# Morpheus_conector.net
KiCad netlist of a schematic drawn in Altium Designer
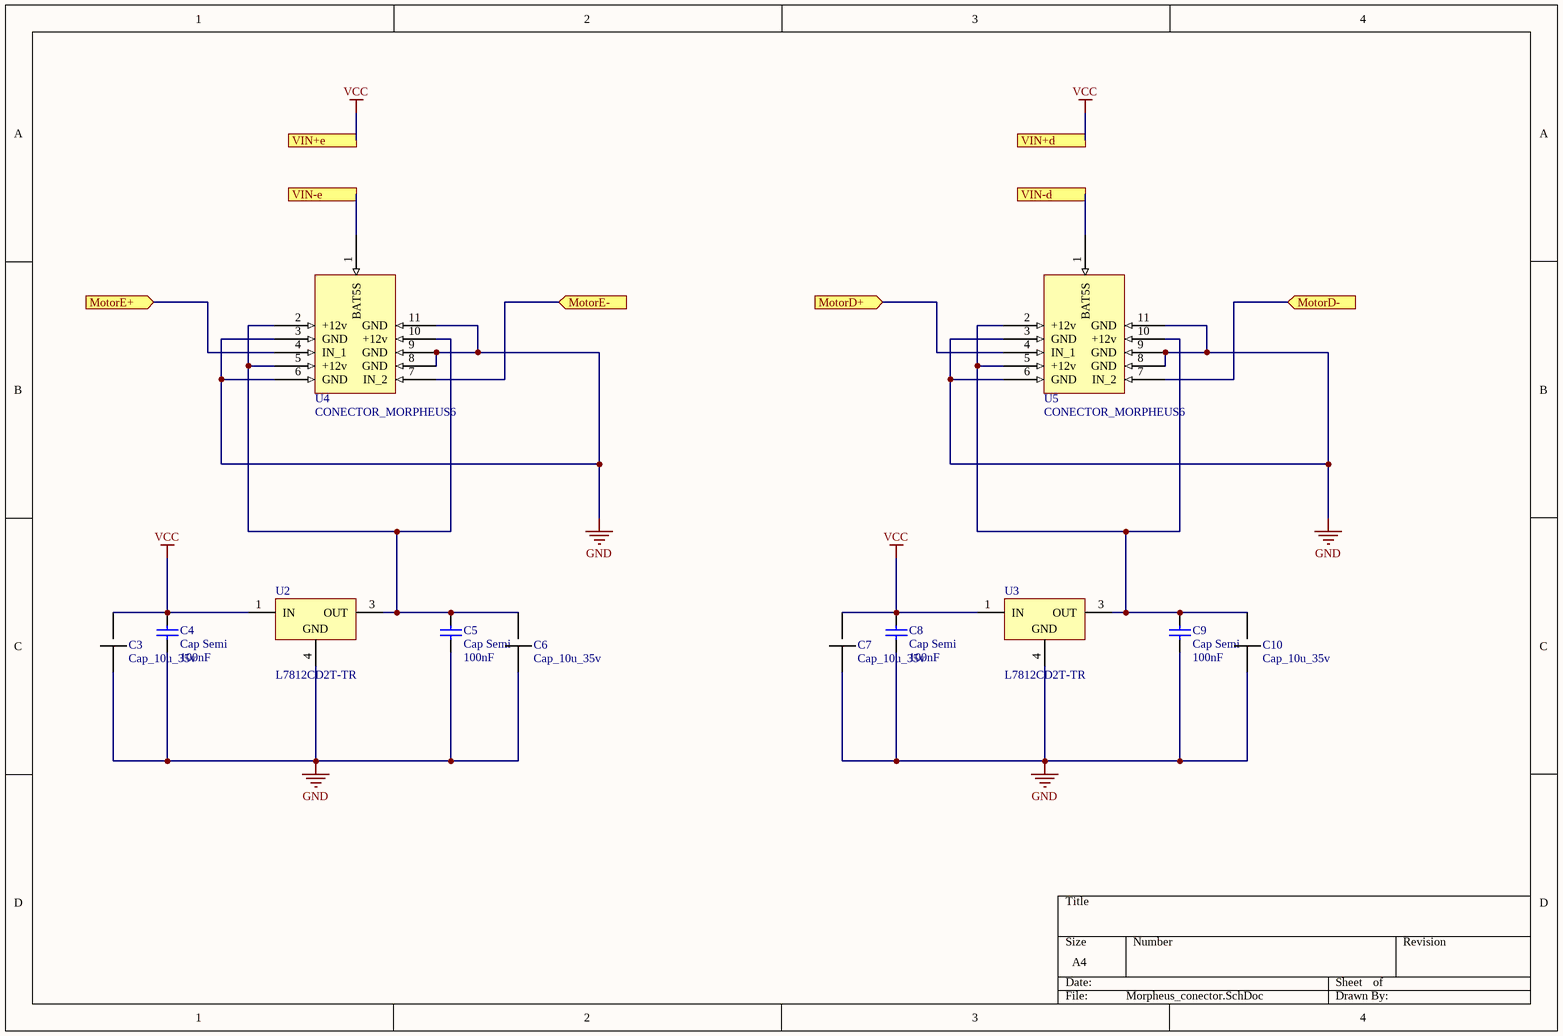
[diagram p0: Morpheus_conector.SchDoc]

(export (version "E")
  (design (tool "Eeschema 10.0.6"))
  (components
    (comp (ref "C3")
      (value "Cap_10u_35v")
      (footprint "Passives:CAP POL 2917/7343")
      (libsource (lib "LibSanhaço2017") (part "Cap_10u_35v"))
    )
    (comp (ref "C4")
      (value "Cap Semi")
      (footprint "C1206")
      (description "Capacitor (Semiconductor SIM Model)")
      (fields (field (name "ALTIUM_VALUE") "100nF") (field (name "PUBLISHER") "Altium Limited"))
      (libsource (lib "Miscellaneous Devices") (part "Cap Semi"))
    )
    (comp (ref "C5")
      (value "Cap Semi")
      (footprint "C1206")
      (description "Capacitor (Semiconductor SIM Model)")
      (fields (field (name "ALTIUM_VALUE") "100nF") (field (name "PUBLISHER") "Altium Limited"))
      (libsource (lib "Miscellaneous Devices") (part "Cap Semi"))
    )
    (comp (ref "C6")
      (value "Cap_10u_35v")
      (footprint "Passives:CAP POL 2917/7343")
      (libsource (lib "LibSanhaço2017") (part "Cap_10u_35v"))
    )
    (comp (ref "C7")
      (value "Cap_10u_35v")
      (footprint "Passives:CAP POL 2917/7343")
      (libsource (lib "LibSanhaço2017") (part "Cap_10u_35v"))
    )
    (comp (ref "C8")
      (value "Cap Semi")
      (footprint "C1206")
      (description "Capacitor (Semiconductor SIM Model)")
      (fields (field (name "ALTIUM_VALUE") "100nF") (field (name "PUBLISHER") "Altium Limited"))
      (libsource (lib "Miscellaneous Devices") (part "Cap Semi"))
    )
    (comp (ref "C9")
      (value "Cap Semi")
      (footprint "C1206")
      (description "Capacitor (Semiconductor SIM Model)")
      (fields (field (name "ALTIUM_VALUE") "100nF") (field (name "PUBLISHER") "Altium Limited"))
      (libsource (lib "Miscellaneous Devices") (part "Cap Semi"))
    )
    (comp (ref "C10")
      (value "Cap_10u_35v")
      (footprint "Passives:CAP POL 2917/7343")
      (libsource (lib "LibSanhaço2017") (part "Cap_10u_35v"))
    )
    (comp (ref "U2")
      (value "L7812CD2T-TR")
      (footprint "TO-263_N")
      (description "Positive Voltage Regulator, 3-Pin D2PAK, Tape and Reel")
      (libsource (lib "L7812CD2T-TR") (part "CMP-0244-00182-1"))
    )
    (comp (ref "U3")
      (value "L7812CD2T-TR")
      (footprint "TO-263_N")
      (description "Positive Voltage Regulator, 3-Pin D2PAK, Tape and Reel")
      (libsource (lib "L7812CD2T-TR") (part "CMP-0244-00182-1"))
    )
    (comp (ref "U4")
      (value "CONECTOR_MORPHEUS6")
      (libsource (lib "Morpheus_CONECTOR") (part "CONECTOR_MORPHEUS6"))
    )
    (comp (ref "U5")
      (value "CONECTOR_MORPHEUS6")
      (libsource (lib "Morpheus_CONECTOR") (part "CONECTOR_MORPHEUS6"))
    )
  )
  (nets
    (net (code "1") (name "/MotorD+") (class "Default")
      (node (ref "U5") (pin "4") (pinfunction "IN_1_4") (pintype "input"))
    )
    (net (code "2") (name "/MotorD-") (class "Default")
      (node (ref "U5") (pin "7") (pinfunction "IN_2_7") (pintype "input"))
    )
    (net (code "3") (name "/MotorE+") (class "Default")
      (node (ref "U4") (pin "4") (pinfunction "IN_1_4") (pintype "input"))
    )
    (net (code "4") (name "/MotorE-") (class "Default")
      (node (ref "U4") (pin "7") (pinfunction "IN_2_7") (pintype "input"))
    )
    (net (code "5") (name "/VIN-d") (class "Default")
      (node (ref "U5") (pin "1") (pinfunction "BAT5S_1") (pintype "input"))
    )
    (net (code "6") (name "/VIN-e") (class "Default")
      (node (ref "U4") (pin "1") (pinfunction "BAT5S_1") (pintype "input"))
    )
    (net (code "7") (name "GND") (class "Default")
      (node (ref "C10") (pin "1") (pinfunction "1_1") (pintype "passive"))
      (node (ref "C3") (pin "1") (pinfunction "1_1") (pintype "passive"))
      (node (ref "C4") (pin "1") (pinfunction "1_1") (pintype "passive"))
      (node (ref "C5") (pin "1") (pinfunction "1_1") (pintype "passive"))
      (node (ref "C6") (pin "1") (pinfunction "1_1") (pintype "passive"))
      (node (ref "C7") (pin "1") (pinfunction "1_1") (pintype "passive"))
      (node (ref "C8") (pin "1") (pinfunction "1_1") (pintype "passive"))
      (node (ref "C9") (pin "1") (pinfunction "1_1") (pintype "passive"))
      (node (ref "U2") (pin "4") (pinfunction "GND_4") (pintype "power_in"))
      (node (ref "U3") (pin "4") (pinfunction "GND_4") (pintype "power_in"))
      (node (ref "U4") (pin "11") (pinfunction "GND_11") (pintype "input"))
      (node (ref "U4") (pin "3") (pinfunction "GND_3") (pintype "input"))
      (node (ref "U4") (pin "6") (pinfunction "GND_6") (pintype "input"))
      (node (ref "U4") (pin "8") (pinfunction "GND_8") (pintype "input"))
      (node (ref "U4") (pin "9") (pinfunction "GND_9") (pintype "input"))
      (node (ref "U5") (pin "11") (pinfunction "GND_11") (pintype "input"))
      (node (ref "U5") (pin "3") (pinfunction "GND_3") (pintype "input"))
      (node (ref "U5") (pin "6") (pinfunction "GND_6") (pintype "input"))
      (node (ref "U5") (pin "8") (pinfunction "GND_8") (pintype "input"))
      (node (ref "U5") (pin "9") (pinfunction "GND_9") (pintype "input"))
    )
    (net (code "8") (name "Net-(U2-OUT)") (class "Default")
      (node (ref "C5") (pin "2") (pinfunction "2_2") (pintype "passive"))
      (node (ref "C6") (pin "2") (pinfunction "2_2") (pintype "passive"))
      (node (ref "U2") (pin "3") (pinfunction "OUT_3") (pintype "power_in"))
      (node (ref "U4") (pin "10") (pinfunction "+12v_10") (pintype "input"))
      (node (ref "U4") (pin "2") (pinfunction "+12v_2") (pintype "input"))
      (node (ref "U4") (pin "5") (pinfunction "+12v_5") (pintype "input"))
    )
    (net (code "9") (name "Net-(U3-OUT)") (class "Default")
      (node (ref "C10") (pin "2") (pinfunction "2_2") (pintype "passive"))
      (node (ref "C9") (pin "2") (pinfunction "2_2") (pintype "passive"))
      (node (ref "U3") (pin "3") (pinfunction "OUT_3") (pintype "power_in"))
      (node (ref "U5") (pin "10") (pinfunction "+12v_10") (pintype "input"))
      (node (ref "U5") (pin "2") (pinfunction "+12v_2") (pintype "input"))
      (node (ref "U5") (pin "5") (pinfunction "+12v_5") (pintype "input"))
    )
    (net (code "10") (name "VCC") (class "Default")
      (node (ref "C3") (pin "2") (pinfunction "2_2") (pintype "passive"))
      (node (ref "C4") (pin "2") (pinfunction "2_2") (pintype "passive"))
      (node (ref "C7") (pin "2") (pinfunction "2_2") (pintype "passive"))
      (node (ref "C8") (pin "2") (pinfunction "2_2") (pintype "passive"))
      (node (ref "U2") (pin "1") (pinfunction "IN_1") (pintype "power_in"))
      (node (ref "U3") (pin "1") (pinfunction "IN_1") (pintype "power_in"))
    )
  )
)
